# Channel.net
KiCad netlist of a schematic drawn in Altium Designer
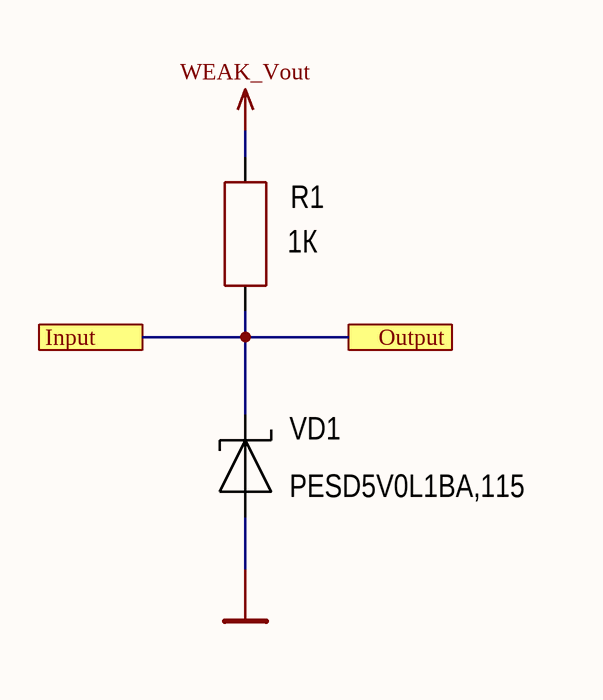
[diagram p0: Channel.SchDoc]

(export (version "E")
  (design (tool "Eeschema 10.0.6"))
  (components
    (comp (ref "R1")
      (value "1К")
      (footprint "RES: 0805")
      (fields
        (field (name "MANUFACTURER") "Yageo")
        (field (name "PARTNUMBER") "RC0805JR-07100RL")
        (field (name "VALUEMANUFACTURERPARTNUMBER") "Resistor film, 1К, ±5%, 0805, 0.125W, -55...+125°C")
      )
      (libsource (lib "Resistor") (part "Resistor_0805"))
    )
    (comp (ref "VD1")
      (value "~")
      (footprint "DIODE: SOD323")
      (description "https://www.chipdip.ru/product/srr1208-330yl")
      (fields
        (field (name "MANUFACTURER") "Diodes Incorporated")
        (field (name "VALUEMANUFACTURERPARTNUMBER") "Schottky diode, 80V, 500mA, 1V, 15pF, SOD-123, -55...+150°C")
        (field (name "PARTNUMBER") "PESD5V0L1BA,115")
      )
      (libsource (lib "Diode") (part "Schottky_single"))
    )
  )
  (nets
    (net (code "1") (name "/Input") (class "Default")
      (node (ref "R1") (pin "1") (pinfunction "1_1") (pintype "passive"))
      (node (ref "VD1") (pin "2") (pinfunction "2_2") (pintype "passive"))
    )
    (net (code "2") (name "GND") (class "Default")
      (node (ref "VD1") (pin "1") (pinfunction "1_1") (pintype "passive"))
    )
    (net (code "3") (name "WEAK_Vout") (class "Default")
      (node (ref "R1") (pin "2") (pinfunction "2_2") (pintype "passive"))
    )
  )
)
